# E-Book_Wing_Rev_A.net
KiCad netlist of a schematic drawn in EAGLE
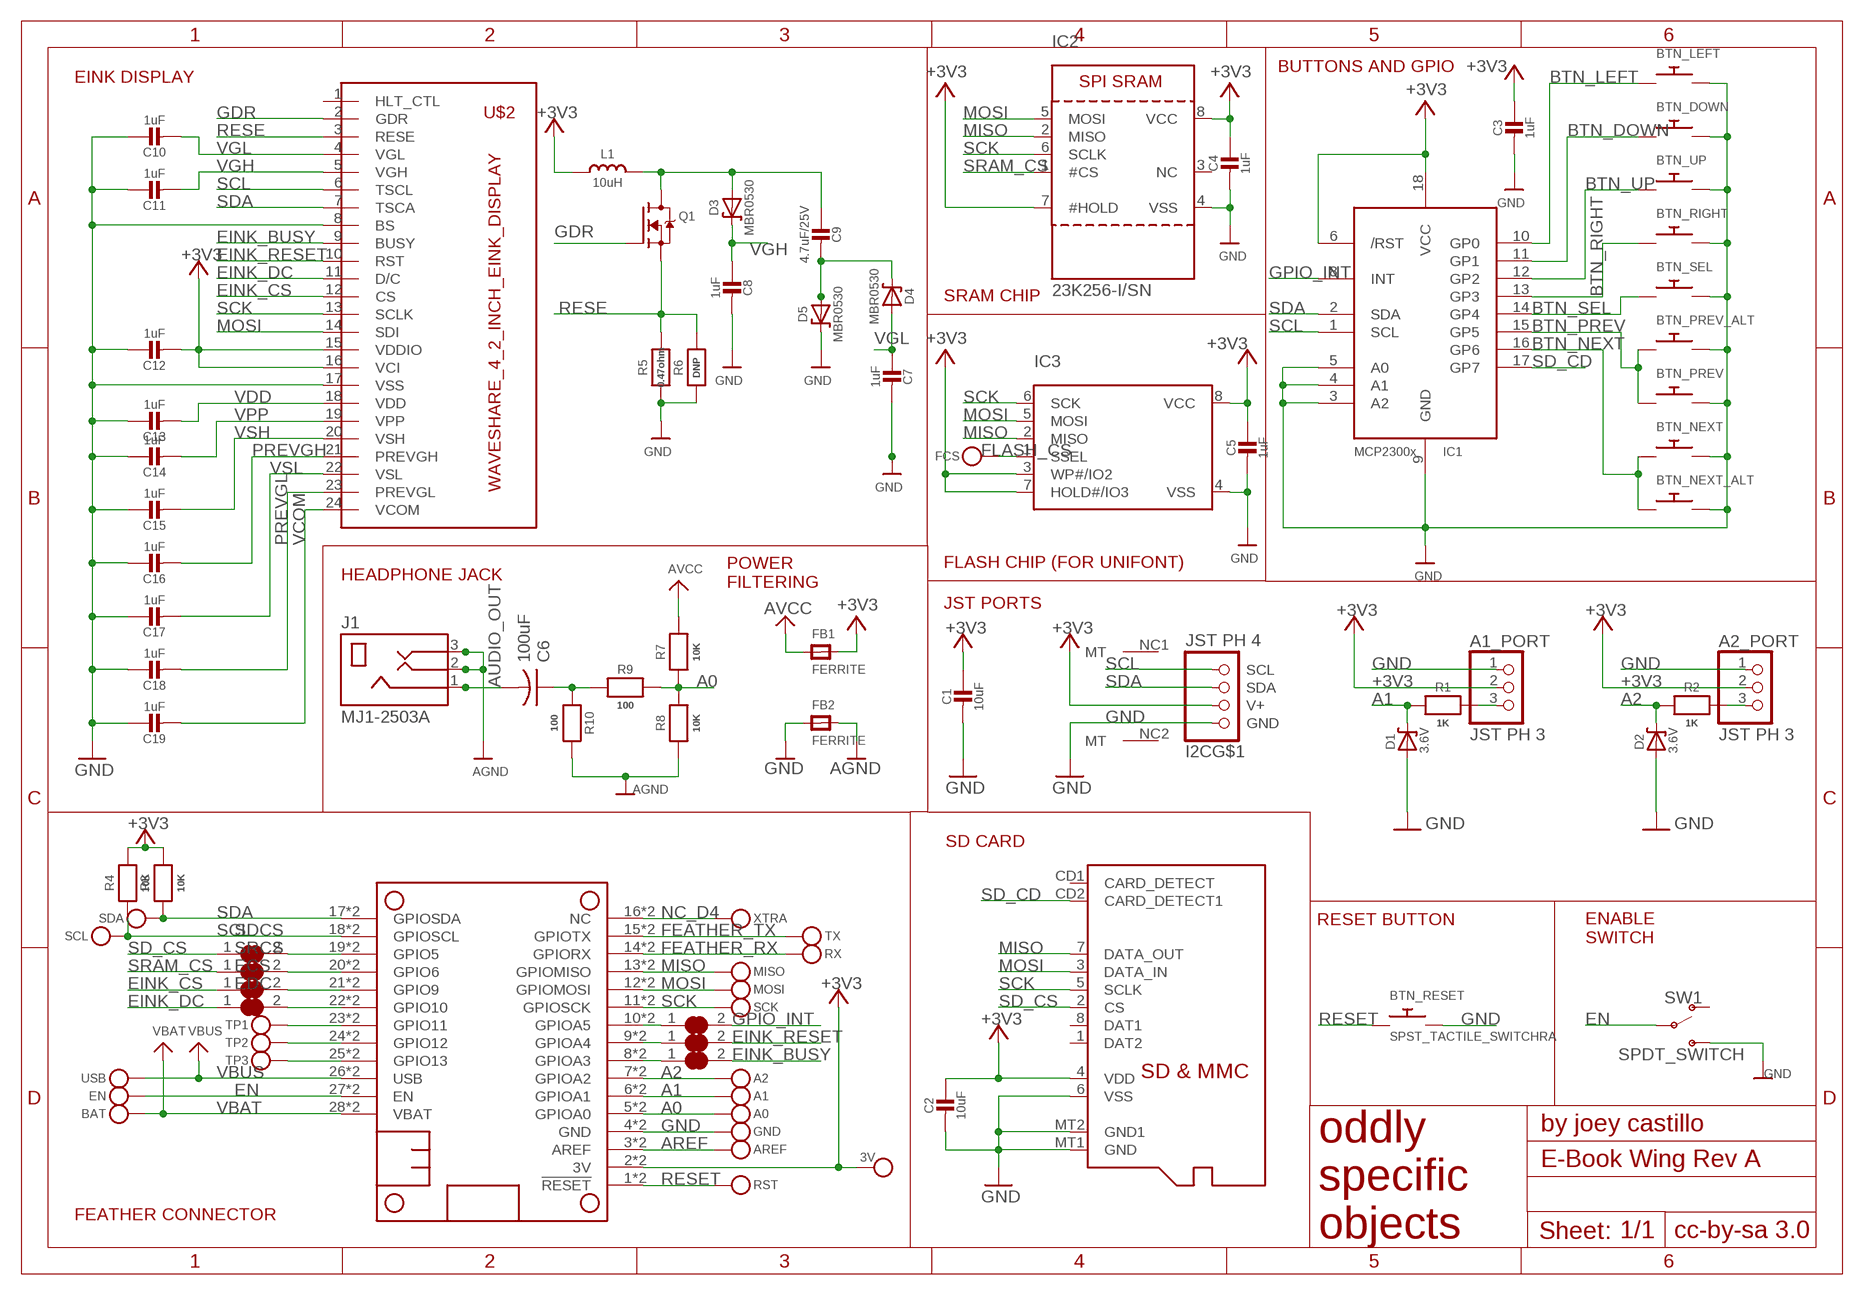
[diagram p0: schematic, sheet 1]

(export (version "E")
  (design (tool "Eeschema 10.0.6"))
  (components
    (comp (ref "3V")
      (value "MICROBUILDER_TESTPOINT1.5X2.0MM_NOCREAM")
      (footprint "eagle-import:MICROBUILDER_PAD-1.5X2.0")
      (libsource (lib "eagle-import") (part "MICROBUILDER_TESTPOINT1.5X2.0MM_NOCREAM"))
    )
    (comp (ref "A0")
      (value "MICROBUILDER_TESTPOINT1.5X2.0MM_NOCREAM")
      (footprint "eagle-import:MICROBUILDER_PAD-1.5X2.0")
      (libsource (lib "eagle-import") (part "MICROBUILDER_TESTPOINT1.5X2.0MM_NOCREAM"))
    )
    (comp (ref "A1")
      (value "MICROBUILDER_TESTPOINT1.5X2.0MM_NOCREAM")
      (footprint "eagle-import:MICROBUILDER_PAD-1.5X2.0")
      (libsource (lib "eagle-import") (part "MICROBUILDER_TESTPOINT1.5X2.0MM_NOCREAM"))
    )
    (comp (ref "A1_PORT")
      (value "JST PH 3")
      (footprint "eagle-import:JSTPH3")
      (libsource (lib "eagle-import") (part "CON_JST_PH_3PIN"))
    )
    (comp (ref "A2")
      (value "MICROBUILDER_TESTPOINT1.5X2.0MM_NOCREAM")
      (footprint "eagle-import:MICROBUILDER_PAD-1.5X2.0")
      (libsource (lib "eagle-import") (part "MICROBUILDER_TESTPOINT1.5X2.0MM_NOCREAM"))
    )
    (comp (ref "A2_PORT")
      (value "JST PH 3")
      (footprint "eagle-import:JSTPH3")
      (libsource (lib "eagle-import") (part "CON_JST_PH_3PIN"))
    )
    (comp (ref "AREF")
      (value "MICROBUILDER_TESTPOINT1.5X2.0MM_NOCREAM")
      (footprint "eagle-import:MICROBUILDER_PAD-1.5X2.0")
      (libsource (lib "eagle-import") (part "MICROBUILDER_TESTPOINT1.5X2.0MM_NOCREAM"))
    )
    (comp (ref "BAT")
      (value "MICROBUILDER_TESTPOINT1.5X2.0MM_NOCREAM")
      (footprint "eagle-import:MICROBUILDER_PAD-1.5X2.0")
      (libsource (lib "eagle-import") (part "MICROBUILDER_TESTPOINT1.5X2.0MM_NOCREAM"))
    )
    (comp (ref "BTN_DOWN")
      (value "MJTP1250_SPST_SWITCH")
      (footprint "eagle-import:MJTP1250")
      (libsource (lib "eagle-import") (part "MJTP1250_SPST_SWITCH"))
    )
    (comp (ref "BTN_LEFT")
      (value "MJTP1250_SPST_SWITCH")
      (footprint "eagle-import:MJTP1250")
      (libsource (lib "eagle-import") (part "MJTP1250_SPST_SWITCH"))
    )
    (comp (ref "BTN_NEXT")
      (value "MJTP1250_SPST_SWITCH")
      (footprint "eagle-import:MJTP1250")
      (libsource (lib "eagle-import") (part "MJTP1250_SPST_SWITCH"))
    )
    (comp (ref "BTN_NEXT_ALT")
      (value "SPST_TACTILE_SWITCHRA")
      (footprint "eagle-import:TL3330AF130QG")
      (libsource (lib "eagle-import") (part "SPST_TACTILE_SWITCHRA"))
    )
    (comp (ref "BTN_PREV")
      (value "MJTP1250_SPST_SWITCH")
      (footprint "eagle-import:MJTP1250")
      (libsource (lib "eagle-import") (part "MJTP1250_SPST_SWITCH"))
    )
    (comp (ref "BTN_PREV_ALT")
      (value "SPST_TACTILE_SWITCHRA")
      (footprint "eagle-import:TL3330AF130QG")
      (libsource (lib "eagle-import") (part "SPST_TACTILE_SWITCHRA"))
    )
    (comp (ref "BTN_RESET")
      (value "SPST_TACTILE_SWITCHRA")
      (footprint "eagle-import:TL3330AF130QG")
      (libsource (lib "eagle-import") (part "SPST_TACTILE_SWITCHRA"))
    )
    (comp (ref "BTN_RIGHT")
      (value "MJTP1250_SPST_SWITCH")
      (footprint "eagle-import:MJTP1250")
      (libsource (lib "eagle-import") (part "MJTP1250_SPST_SWITCH"))
    )
    (comp (ref "BTN_SEL")
      (value "MJTP1250_SPST_SWITCH")
      (footprint "eagle-import:MJTP1250")
      (libsource (lib "eagle-import") (part "MJTP1250_SPST_SWITCH"))
    )
    (comp (ref "BTN_UP")
      (value "MJTP1250_SPST_SWITCH")
      (footprint "eagle-import:MJTP1250")
      (libsource (lib "eagle-import") (part "MJTP1250_SPST_SWITCH"))
    )
    (comp (ref "C1")
      (value "10uF")
      (footprint "eagle-import:0805-NO")
      (libsource (lib "eagle-import") (part "CAP_CERAMIC0805-NOOUTLINE"))
    )
    (comp (ref "C2")
      (value "10uF")
      (footprint "eagle-import:0805_10MGAP")
      (libsource (lib "eagle-import") (part "CAP_CERAMIC0805_10MGAP"))
    )
    (comp (ref "C3")
      (value "1uF")
      (footprint "eagle-import:0805_10MGAP")
      (libsource (lib "eagle-import") (part "CAP_CERAMIC0805_10MGAP"))
    )
    (comp (ref "C4")
      (value "1uF")
      (footprint "eagle-import:0805_10MGAP")
      (libsource (lib "eagle-import") (part "CAP_CERAMIC0805_10MGAP"))
    )
    (comp (ref "C5")
      (value "1uF")
      (footprint "eagle-import:0805_10MGAP")
      (libsource (lib "eagle-import") (part "CAP_CERAMIC0805_10MGAP"))
    )
    (comp (ref "C6")
      (value "100uF")
      (footprint "eagle-import:C1210")
      (libsource (lib "eagle-import") (part "C-USC1210"))
    )
    (comp (ref "C7")
      (value "1uF")
      (footprint "eagle-import:0805-NO")
      (libsource (lib "eagle-import") (part "CAP_CERAMIC0805-NOOUTLINE"))
    )
    (comp (ref "C8")
      (value "1uF")
      (footprint "eagle-import:0805-NO")
      (libsource (lib "eagle-import") (part "CAP_CERAMIC0805-NOOUTLINE"))
    )
    (comp (ref "C9")
      (value "4.7uF/25V")
      (footprint "eagle-import:0805-NO")
      (libsource (lib "eagle-import") (part "CAP_CERAMIC0805-NOOUTLINE"))
    )
    (comp (ref "C10")
      (value "1uF")
      (footprint "eagle-import:0805-NO")
      (libsource (lib "eagle-import") (part "CAP_CERAMIC0805-NOOUTLINE"))
    )
    (comp (ref "C11")
      (value "1uF")
      (footprint "eagle-import:0805-NO")
      (libsource (lib "eagle-import") (part "CAP_CERAMIC0805-NOOUTLINE"))
    )
    (comp (ref "C12")
      (value "1uF")
      (footprint "eagle-import:0805-NO")
      (libsource (lib "eagle-import") (part "CAP_CERAMIC0805-NOOUTLINE"))
    )
    (comp (ref "C13")
      (value "1uF")
      (footprint "eagle-import:0805-NO")
      (libsource (lib "eagle-import") (part "CAP_CERAMIC0805-NOOUTLINE"))
    )
    (comp (ref "C14")
      (value "1uF")
      (footprint "eagle-import:0805-NO")
      (libsource (lib "eagle-import") (part "CAP_CERAMIC0805-NOOUTLINE"))
    )
    (comp (ref "C15")
      (value "1uF")
      (footprint "eagle-import:0805-NO")
      (libsource (lib "eagle-import") (part "CAP_CERAMIC0805-NOOUTLINE"))
    )
    (comp (ref "C16")
      (value "1uF")
      (footprint "eagle-import:0805-NO")
      (libsource (lib "eagle-import") (part "CAP_CERAMIC0805-NOOUTLINE"))
    )
    (comp (ref "C17")
      (value "1uF")
      (footprint "eagle-import:0805-NO")
      (libsource (lib "eagle-import") (part "CAP_CERAMIC0805-NOOUTLINE"))
    )
    (comp (ref "C18")
      (value "1uF")
      (footprint "eagle-import:0805-NO")
      (libsource (lib "eagle-import") (part "CAP_CERAMIC0805-NOOUTLINE"))
    )
    (comp (ref "C19")
      (value "1uF")
      (footprint "eagle-import:0805-NO")
      (libsource (lib "eagle-import") (part "CAP_CERAMIC0805-NOOUTLINE"))
    )
    (comp (ref "D1")
      (value "3.6V")
      (footprint "eagle-import:SOD-123")
      (libsource (lib "eagle-import") (part "DIODE-ZENERSOD123"))
    )
    (comp (ref "D2")
      (value "3.6V")
      (footprint "eagle-import:SOD-123")
      (libsource (lib "eagle-import") (part "DIODE-ZENERSOD123"))
    )
    (comp (ref "D3")
      (value "MBR0530")
      (footprint "eagle-import:SOD-123")
      (libsource (lib "eagle-import") (part "DIODE-SCHOTTKYSOD-123"))
    )
    (comp (ref "D4")
      (value "MBR0530")
      (footprint "eagle-import:SOD-123")
      (libsource (lib "eagle-import") (part "DIODE-SCHOTTKYSOD-123"))
    )
    (comp (ref "D5")
      (value "MBR0530")
      (footprint "eagle-import:SOD-123")
      (libsource (lib "eagle-import") (part "DIODE-SCHOTTKYSOD-123"))
    )
    (comp (ref "EBSY")
      (value "MICROBUILDER_SOLDERJUMPER_CLOSED")
      (footprint "eagle-import:MICROBUILDER_SOLDERJUMPER_CLOSEDWIRE")
      (libsource (lib "eagle-import") (part "MICROBUILDER_SOLDERJUMPER_CLOSED"))
    )
    (comp (ref "ECS")
      (value "MICROBUILDER_SOLDERJUMPER_CLOSED")
      (footprint "eagle-import:MICROBUILDER_SOLDERJUMPER_CLOSEDWIRE")
      (libsource (lib "eagle-import") (part "MICROBUILDER_SOLDERJUMPER_CLOSED"))
    )
    (comp (ref "EDC")
      (value "MICROBUILDER_SOLDERJUMPER_CLOSED")
      (footprint "eagle-import:MICROBUILDER_SOLDERJUMPER_CLOSEDWIRE")
      (libsource (lib "eagle-import") (part "MICROBUILDER_SOLDERJUMPER_CLOSED"))
    )
    (comp (ref "EN")
      (value "MICROBUILDER_TESTPOINT1.5X2.0MM_NOCREAM")
      (footprint "eagle-import:MICROBUILDER_PAD-1.5X2.0")
      (libsource (lib "eagle-import") (part "MICROBUILDER_TESTPOINT1.5X2.0MM_NOCREAM"))
    )
    (comp (ref "ERST")
      (value "MICROBUILDER_SOLDERJUMPER_CLOSED")
      (footprint "eagle-import:MICROBUILDER_SOLDERJUMPER_CLOSEDWIRE")
      (libsource (lib "eagle-import") (part "MICROBUILDER_SOLDERJUMPER_CLOSED"))
    )
    (comp (ref "FB1")
      (value "FERRITE")
      (footprint "eagle-import:0805")
      (libsource (lib "eagle-import") (part "FERRITE0805"))
    )
    (comp (ref "FB2")
      (value "FERRITE")
      (footprint "eagle-import:0805")
      (libsource (lib "eagle-import") (part "FERRITE0805"))
    )
    (comp (ref "FCS")
      (value "MICROBUILDER_TESTPOINTPAD1MM")
      (footprint "eagle-import:MICROBUILDER_TESTPOINT_PAD_1MM")
      (libsource (lib "eagle-import") (part "MICROBUILDER_TESTPOINTPAD1MM"))
    )
    (comp (ref "GND")
      (value "MICROBUILDER_TESTPOINT1.5X2.0MM_NOCREAM")
      (footprint "eagle-import:MICROBUILDER_PAD-1.5X2.0")
      (libsource (lib "eagle-import") (part "MICROBUILDER_TESTPOINT1.5X2.0MM_NOCREAM"))
    )
    (comp (ref "I2C")
      (value "JST PH 4")
      (footprint "eagle-import:JSTPH4")
      (libsource (lib "eagle-import") (part "STEMMA_I2C_RASMT"))
    )
    (comp (ref "IC1")
      (value "MCP23008/SO")
      (footprint "eagle-import:SO18W")
      (libsource (lib "eagle-import") (part "MCP23008/SO"))
    )
    (comp (ref "IC2")
      (value "23K256-I/SN")
      (footprint "eagle-import:SOIC8_150MIL")
      (libsource (lib "eagle-import") (part "SRAM_SPI_SOIC8"))
    )
    (comp (ref "IC3")
      (value "MICROBUILDER_SPIFLASH_SOIC8")
      (footprint "eagle-import:MICROBUILDER_SOIC8_150MIL")
      (libsource (lib "eagle-import") (part "MICROBUILDER_SPIFLASH_SOIC8"))
    )
    (comp (ref "INT")
      (value "MICROBUILDER_SOLDERJUMPER_CLOSED")
      (footprint "eagle-import:MICROBUILDER_SOLDERJUMPER_CLOSEDWIRE")
      (libsource (lib "eagle-import") (part "MICROBUILDER_SOLDERJUMPER_CLOSED"))
    )
    (comp (ref "J1")
      (value "MJ1-2503A")
      (footprint "eagle-import:CUI_MJ1-2503A")
      (fields (field (name "DIGI-KEY_PART_NUMBER") "CP1-2503AM-ND") (field (name "MF") "CUI Inc."))
      (libsource (lib "eagle-import") (part "MJ1-2503A"))
    )
    (comp (ref "L1")
      (value "10uH")
      (footprint "eagle-import:INDUCTOR_4X4MM_NR401")
      (libsource (lib "eagle-import") (part "INDUCTORNR401"))
    )
    (comp (ref "MICROSD")
      (value "MICROSD")
      (footprint "eagle-import:MICROSD")
      (libsource (lib "eagle-import") (part "MICROSD"))
    )
    (comp (ref "MISO")
      (value "MICROBUILDER_TESTPOINT1.5X2.0MM_NOCREAM")
      (footprint "eagle-import:MICROBUILDER_PAD-1.5X2.0")
      (libsource (lib "eagle-import") (part "MICROBUILDER_TESTPOINT1.5X2.0MM_NOCREAM"))
    )
    (comp (ref "MOSI")
      (value "MICROBUILDER_TESTPOINT1.5X2.0MM_NOCREAM")
      (footprint "eagle-import:MICROBUILDER_PAD-1.5X2.0")
      (libsource (lib "eagle-import") (part "MICROBUILDER_TESTPOINT1.5X2.0MM_NOCREAM"))
    )
    (comp (ref "MS1")
      (value "MICROBUILDER_FEATHERWING_SMTDUAL")
      (footprint "eagle-import:MICROBUILDER_FEATHERWING_SMT2")
      (libsource (lib "eagle-import") (part "MICROBUILDER_FEATHERWING_SMTDUAL"))
    )
    (comp (ref "Q1")
      (value "IRLML0100")
      (footprint "eagle-import:SOT23-3")
      (libsource (lib "eagle-import") (part "IRLML2060TRPBF"))
    )
    (comp (ref "R1")
      (value "1K")
      (footprint "eagle-import:_0805MP")
      (libsource (lib "eagle-import") (part "RESISTOR_0805MP"))
    )
    (comp (ref "R2")
      (value "1K")
      (footprint "eagle-import:_0805MP")
      (libsource (lib "eagle-import") (part "RESISTOR_0805MP"))
    )
    (comp (ref "R3")
      (value "10K")
      (footprint "eagle-import:_0805MP")
      (libsource (lib "eagle-import") (part "RESISTOR_0805MP"))
    )
    (comp (ref "R4")
      (value "10K")
      (footprint "eagle-import:_0805MP")
      (libsource (lib "eagle-import") (part "RESISTOR_0805MP"))
    )
    (comp (ref "R5")
      (value "0.47ohm")
      (footprint "eagle-import:0805_10MGAP")
      (libsource (lib "eagle-import") (part "RESISTOR0805_10MGAP"))
    )
    (comp (ref "R6")
      (value "DNP")
      (footprint "eagle-import:0805_10MGAP")
      (libsource (lib "eagle-import") (part "RESISTOR0805_10MGAP"))
    )
    (comp (ref "R7")
      (value "10K")
      (footprint "eagle-import:_0805MP")
      (libsource (lib "eagle-import") (part "RESISTOR_0805MP"))
    )
    (comp (ref "R8")
      (value "10K")
      (footprint "eagle-import:_0805MP")
      (libsource (lib "eagle-import") (part "RESISTOR_0805MP"))
    )
    (comp (ref "R9")
      (value "100")
      (footprint "eagle-import:_0805MP")
      (libsource (lib "eagle-import") (part "RESISTOR_0805MP"))
    )
    (comp (ref "R10")
      (value "100")
      (footprint "eagle-import:_0805MP")
      (libsource (lib "eagle-import") (part "RESISTOR_0805MP"))
    )
    (comp (ref "RST")
      (value "MICROBUILDER_TESTPOINT1.5X2.0MM_NOCREAM")
      (footprint "eagle-import:MICROBUILDER_PAD-1.5X2.0")
      (libsource (lib "eagle-import") (part "MICROBUILDER_TESTPOINT1.5X2.0MM_NOCREAM"))
    )
    (comp (ref "RX")
      (value "MICROBUILDER_TESTPOINT1.5X2.0MM_NOCREAM")
      (footprint "eagle-import:MICROBUILDER_PAD-1.5X2.0")
      (libsource (lib "eagle-import") (part "MICROBUILDER_TESTPOINT1.5X2.0MM_NOCREAM"))
    )
    (comp (ref "SCK")
      (value "MICROBUILDER_TESTPOINT1.5X2.0MM_NOCREAM")
      (footprint "eagle-import:MICROBUILDER_PAD-1.5X2.0")
      (libsource (lib "eagle-import") (part "MICROBUILDER_TESTPOINT1.5X2.0MM_NOCREAM"))
    )
    (comp (ref "SCL")
      (value "MICROBUILDER_TESTPOINT1.5X2.0MM_NOCREAM")
      (footprint "eagle-import:MICROBUILDER_PAD-1.5X2.0")
      (libsource (lib "eagle-import") (part "MICROBUILDER_TESTPOINT1.5X2.0MM_NOCREAM"))
    )
    (comp (ref "SDA")
      (value "MICROBUILDER_TESTPOINT1.5X2.0MM_NOCREAM")
      (footprint "eagle-import:MICROBUILDER_PAD-1.5X2.0")
      (libsource (lib "eagle-import") (part "MICROBUILDER_TESTPOINT1.5X2.0MM_NOCREAM"))
    )
    (comp (ref "SDCS")
      (value "MICROBUILDER_SOLDERJUMPER_CLOSED")
      (footprint "eagle-import:MICROBUILDER_SOLDERJUMPER_CLOSEDWIRE")
      (libsource (lib "eagle-import") (part "MICROBUILDER_SOLDERJUMPER_CLOSED"))
    )
    (comp (ref "SRCS")
      (value "MICROBUILDER_SOLDERJUMPER_CLOSED")
      (footprint "eagle-import:MICROBUILDER_SOLDERJUMPER_CLOSEDWIRE")
      (libsource (lib "eagle-import") (part "MICROBUILDER_SOLDERJUMPER_CLOSED"))
    )
    (comp (ref "SW1")
      (value "SPDT_SWITCH")
      (footprint "eagle-import:A10767")
      (libsource (lib "eagle-import") (part "SPDT_SWITCH"))
    )
    (comp (ref "TP1")
      (value "MICROBUILDER_TESTPOINT1.5X2.0MM_NOCREAM")
      (footprint "eagle-import:MICROBUILDER_PAD-1.5X2.0")
      (libsource (lib "eagle-import") (part "MICROBUILDER_TESTPOINT1.5X2.0MM_NOCREAM"))
    )
    (comp (ref "TP2")
      (value "MICROBUILDER_TESTPOINT1.5X2.0MM_NOCREAM")
      (footprint "eagle-import:MICROBUILDER_PAD-1.5X2.0")
      (libsource (lib "eagle-import") (part "MICROBUILDER_TESTPOINT1.5X2.0MM_NOCREAM"))
    )
    (comp (ref "TP3")
      (value "MICROBUILDER_TESTPOINT1.5X2.0MM_NOCREAM")
      (footprint "eagle-import:MICROBUILDER_PAD-1.5X2.0")
      (libsource (lib "eagle-import") (part "MICROBUILDER_TESTPOINT1.5X2.0MM_NOCREAM"))
    )
    (comp (ref "TX")
      (value "MICROBUILDER_TESTPOINT1.5X2.0MM_NOCREAM")
      (footprint "eagle-import:MICROBUILDER_PAD-1.5X2.0")
      (libsource (lib "eagle-import") (part "MICROBUILDER_TESTPOINT1.5X2.0MM_NOCREAM"))
    )
    (comp (ref "U$2")
      (value "WAVESHARE_4_2_INCH_EINK_DISPLAY")
      (footprint "eagle-import:EINK_DISPLAY_4_2IN")
      (libsource (lib "eagle-import") (part "WAVESHARE_4_2_INCH_EINK_DISPLAY"))
    )
    (comp (ref "USB")
      (value "MICROBUILDER_TESTPOINT1.5X2.0MM_NOCREAM")
      (footprint "eagle-import:MICROBUILDER_PAD-1.5X2.0")
      (libsource (lib "eagle-import") (part "MICROBUILDER_TESTPOINT1.5X2.0MM_NOCREAM"))
    )
    (comp (ref "XTRA")
      (value "MICROBUILDER_TESTPOINT1.5X2.0MM_NOCREAM")
      (footprint "eagle-import:MICROBUILDER_PAD-1.5X2.0")
      (libsource (lib "eagle-import") (part "MICROBUILDER_TESTPOINT1.5X2.0MM_NOCREAM"))
    )
  )
  (nets
    (net (code "1") (name "+3V3") (class "Default")
      (node (ref "3V") (pin "P$1") (pinfunction "P$1_P$1") (pintype "bidirectional"))
      (node (ref "A1_PORT") (pin "2") (pinfunction "2_2") (pintype "passive"))
      (node (ref "A2_PORT") (pin "2") (pinfunction "2_2") (pintype "passive"))
      (node (ref "C1") (pin "1") (pinfunction "1_1") (pintype "passive"))
      (node (ref "C12") (pin "2") (pinfunction "2_2") (pintype "passive"))
      (node (ref "C2") (pin "1") (pinfunction "1_1") (pintype "passive"))
      (node (ref "C3") (pin "1") (pinfunction "1_1") (pintype "passive"))
      (node (ref "C4") (pin "1") (pinfunction "1_1") (pintype "passive"))
      (node (ref "C5") (pin "1") (pinfunction "1_1") (pintype "passive"))
      (node (ref "FB1") (pin "2") (pinfunction "P$2_2") (pintype "passive"))
      (node (ref "I2C") (pin "2") (pinfunction "V+_2") (pintype "passive"))
      (node (ref "IC1") (pin "18") (pinfunction "VCC_18") (pintype "power_in"))
      (node (ref "IC1") (pin "6") (pinfunction "/RST_6") (pintype "input"))
      (node (ref "IC2") (pin "7") (pinfunction "#HOLD_7") (pintype "input"))
      (node (ref "IC2") (pin "8") (pinfunction "VCC_8") (pintype "power_in"))
      (node (ref "IC3") (pin "3") (pinfunction "WP#/IO2_3") (pintype "bidirectional"))
      (node (ref "IC3") (pin "7") (pinfunction "HOLD#/IO3_7") (pintype "bidirectional"))
      (node (ref "IC3") (pin "8") (pinfunction "VCC_8") (pintype "bidirectional"))
      (node (ref "L1") (pin "P$2") (pinfunction "2_P$2") (pintype "passive"))
      (node (ref "MICROSD") (pin "4") (pinfunction "VDD_4") (pintype "power_in"))
      (node (ref "MS1") (pin "2") (pinfunction "3V_2") (pintype "power_in"))
      (node (ref "MS1") (pin "2'") (pinfunction "3V_2'") (pintype "power_in"))
      (node (ref "R3") (pin "1") (pinfunction "1_1") (pintype "passive"))
      (node (ref "R4") (pin "1") (pinfunction "1_1") (pintype "passive"))
      (node (ref "U$2") (pin "15") (pinfunction "VDDIO_15") (pintype "bidirectional"))
      (node (ref "U$2") (pin "16") (pinfunction "VCI_16") (pintype "bidirectional"))
    )
    (net (code "2") (name "/A0") (class "Default")
      (node (ref "A0") (pin "P$1") (pinfunction "P$1_P$1") (pintype "bidirectional"))
      (node (ref "MS1") (pin "5") (pinfunction "GPIOA0_5") (pintype "bidirectional"))
      (node (ref "MS1") (pin "5'") (pinfunction "GPIOA0_5'") (pintype "bidirectional"))
      (node (ref "R7") (pin "2") (pinfunction "2_2") (pintype "passive"))
      (node (ref "R8") (pin "1") (pinfunction "1_1") (pintype "passive"))
      (node (ref "R9") (pin "1") (pinfunction "1_1") (pintype "passive"))
    )
    (net (code "3") (name "/A1") (class "Default")
      (node (ref "A1") (pin "P$1") (pinfunction "P$1_P$1") (pintype "bidirectional"))
      (node (ref "D1") (pin "C") (pinfunction "C_C") (pintype "passive"))
      (node (ref "MS1") (pin "6") (pinfunction "GPIOA1_6") (pintype "bidirectional"))
      (node (ref "MS1") (pin "6'") (pinfunction "GPIOA1_6'") (pintype "bidirectional"))
      (node (ref "R1") (pin "2") (pinfunction "2_2") (pintype "passive"))
    )
    (net (code "4") (name "/A2") (class "Default")
      (node (ref "A2") (pin "P$1") (pinfunction "P$1_P$1") (pintype "bidirectional"))
      (node (ref "D2") (pin "C") (pinfunction "C_C") (pintype "passive"))
      (node (ref "MS1") (pin "7") (pinfunction "GPIOA2_7") (pintype "bidirectional"))
      (node (ref "MS1") (pin "7'") (pinfunction "GPIOA2_7'") (pintype "bidirectional"))
      (node (ref "R2") (pin "2") (pinfunction "2_2") (pintype "passive"))
    )
    (net (code "5") (name "/AREF") (class "Default")
      (node (ref "AREF") (pin "P$1") (pinfunction "P$1_P$1") (pintype "bidirectional"))
      (node (ref "MS1") (pin "3") (pinfunction "AREF_3") (pintype "passive"))
      (node (ref "MS1") (pin "3'") (pinfunction "AREF_3'") (pintype "passive"))
    )
    (net (code "6") (name "/AUDIO_OUT") (class "Default")
      (node (ref "C6") (pin "2") (pinfunction "2_2") (pintype "passive"))
      (node (ref "J1") (pin "1") (pinfunction "1_1") (pintype "passive"))
    )
    (net (code "7") (name "/BTN_DOWN") (class "Default")
      (node (ref "BTN_DOWN") (pin "P$1") (pinfunction "P$1_P$1") (pintype "passive"))
      (node (ref "IC1") (pin "11") (pinfunction "GP1_11") (pintype "bidirectional"))
    )
    (net (code "8") (name "/BTN_LEFT") (class "Default")
      (node (ref "BTN_LEFT") (pin "P$1") (pinfunction "P$1_P$1") (pintype "passive"))
      (node (ref "IC1") (pin "10") (pinfunction "GP0_10") (pintype "bidirectional"))
    )
    (net (code "9") (name "/BTN_NEXT") (class "Default")
      (node (ref "BTN_NEXT") (pin "P$1") (pinfunction "P$1_P$1") (pintype "passive"))
      (node (ref "BTN_NEXT_ALT") (pin "P$1") (pinfunction "P$1_P$1") (pintype "passive"))
      (node (ref "IC1") (pin "16") (pinfunction "GP6_16") (pintype "bidirectional"))
    )
    (net (code "10") (name "/BTN_PREV") (class "Default")
      (node (ref "BTN_PREV") (pin "P$1") (pinfunction "P$1_P$1") (pintype "passive"))
      (node (ref "BTN_PREV_ALT") (pin "P$1") (pinfunction "P$1_P$1") (pintype "passive"))
      (node (ref "IC1") (pin "15") (pinfunction "GP5_15") (pintype "bidirectional"))
    )
    (net (code "11") (name "/BTN_RIGHT") (class "Default")
      (node (ref "BTN_RIGHT") (pin "P$1") (pinfunction "P$1_P$1") (pintype "passive"))
      (node (ref "IC1") (pin "13") (pinfunction "GP3_13") (pintype "bidirectional"))
    )
    (net (code "12") (name "/BTN_SEL") (class "Default")
      (node (ref "BTN_SEL") (pin "P$1") (pinfunction "P$1_P$1") (pintype "passive"))
      (node (ref "IC1") (pin "14") (pinfunction "GP4_14") (pintype "bidirectional"))
    )
    (net (code "13") (name "/BTN_UP") (class "Default")
      (node (ref "BTN_UP") (pin "P$1") (pinfunction "P$1_P$1") (pintype "passive"))
      (node (ref "IC1") (pin "12") (pinfunction "GP2_12") (pintype "bidirectional"))
    )
    (net (code "14") (name "/EINK_BUSY") (class "Default")
      (node (ref "EBSY") (pin "2") (pinfunction "2_2") (pintype "passive"))
      (node (ref "U$2") (pin "9") (pinfunction "BUSY_9") (pintype "bidirectional"))
    )
    (net (code "15") (name "/EINK_CS") (class "Default")
      (node (ref "ECS") (pin "1") (pinfunction "1_1") (pintype "passive"))
      (node (ref "U$2") (pin "12") (pinfunction "CS_12") (pintype "bidirectional"))
    )
    (net (code "16") (name "/EINK_DC") (class "Default")
      (node (ref "EDC") (pin "1") (pinfunction "1_1") (pintype "passive"))
      (node (ref "U$2") (pin "11") (pinfunction "D/C_11") (pintype "bidirectional"))
    )
    (net (code "17") (name "/EINK_RESET") (class "Default")
      (node (ref "ERST") (pin "2") (pinfunction "2_2") (pintype "passive"))
      (node (ref "U$2") (pin "10") (pinfunction "RST_10") (pintype "bidirectional"))
    )
    (net (code "18") (name "/EN") (class "Default")
      (node (ref "EN") (pin "P$1") (pinfunction "P$1_P$1") (pintype "bidirectional"))
      (node (ref "MS1") (pin "27") (pinfunction "EN_27") (pintype "passive"))
      (node (ref "MS1") (pin "27'") (pinfunction "EN_27'") (pintype "passive"))
      (node (ref "SW1") (pin "P$2") (pinfunction "P_P$2") (pintype "passive"))
    )
    (net (code "19") (name "/FEATHER_RX") (class "Default")
      (node (ref "MS1") (pin "14") (pinfunction "GPIORX_14") (pintype "bidirectional"))
      (node (ref "MS1") (pin "14'") (pinfunction "GPIORX_14'") (pintype "bidirectional"))
      (node (ref "RX") (pin "P$1") (pinfunction "P$1_P$1") (pintype "bidirectional"))
    )
    (net (code "20") (name "/FEATHER_TX") (class "Default")
      (node (ref "MS1") (pin "15") (pinfunction "GPIOTX_15") (pintype "bidirectional"))
      (node (ref "MS1") (pin "15'") (pinfunction "GPIOTX_15'") (pintype "bidirectional"))
      (node (ref "TX") (pin "P$1") (pinfunction "P$1_P$1") (pintype "bidirectional"))
    )
    (net (code "21") (name "/FLASH_CS") (class "Default")
      (node (ref "FCS") (pin "P$1") (pinfunction "P$1_P$1") (pintype "bidirectional"))
      (node (ref "IC3") (pin "1") (pinfunction "SSEL_1") (pintype "bidirectional"))
    )
    (net (code "22") (name "/GDR") (class "Default")
      (node (ref "Q1") (pin "1") (pinfunction "G_1") (pintype "bidirectional"))
      (node (ref "U$2") (pin "2") (pinfunction "GDR_2") (pintype "bidirectional"))
    )
    (net (code "23") (name "/GPIO_INT") (class "Default")
      (node (ref "IC1") (pin "8") (pinfunction "INT_8") (pintype "output"))
      (node (ref "INT") (pin "2") (pinfunction "2_2") (pintype "passive"))
    )
    (net (code "24") (name "/MISO") (class "Default")
      (node (ref "IC2") (pin "2") (pinfunction "MISO_2") (pintype "output"))
      (node (ref "IC3") (pin "2") (pinfunction "MISO_2") (pintype "bidirectional"))
      (node (ref "MICROSD") (pin "7") (pinfunction "DATA_OUT_7") (pintype "output"))
      (node (ref "MISO") (pin "P$1") (pinfunction "P$1_P$1") (pintype "bidirectional"))
      (node (ref "MS1") (pin "13") (pinfunction "GPIOMISO_13") (pintype "bidirectional"))
      (node (ref "MS1") (pin "13'") (pinfunction "GPIOMISO_13'") (pintype "bidirectional"))
    )
    (net (code "25") (name "/MOSI") (class "Default")
      (node (ref "IC2") (pin "5") (pinfunction "MOSI_5") (pintype "input"))
      (node (ref "IC3") (pin "5") (pinfunction "MOSI_5") (pintype "bidirectional"))
      (node (ref "MICROSD") (pin "3") (pinfunction "DATA_IN_3") (pintype "input"))
      (node (ref "MOSI") (pin "P$1") (pinfunction "P$1_P$1") (pintype "bidirectional"))
      (node (ref "MS1") (pin "12") (pinfunction "GPIOMOSI_12") (pintype "bidirectional"))
      (node (ref "MS1") (pin "12'") (pinfunction "GPIOMOSI_12'") (pintype "bidirectional"))
      (node (ref "U$2") (pin "14") (pinfunction "SDI_14") (pintype "bidirectional"))
    )
    (net (code "26") (name "/NC_D4") (class "Default")
      (node (ref "MS1") (pin "16") (pinfunction "NC_16") (pintype "passive"))
      (node (ref "MS1") (pin "16'") (pinfunction "NC_16'") (pintype "passive"))
      (node (ref "XTRA") (pin "P$1") (pinfunction "P$1_P$1") (pintype "bidirectional"))
    )
    (net (code "27") (name "/PREVGH") (class "Default")
      (node (ref "C16") (pin "2") (pinfunction "2_2") (pintype "passive"))
      (node (ref "U$2") (pin "21") (pinfunction "PREVGH_21") (pintype "bidirectional"))
    )
    (net (code "28") (name "/PREVGL") (class "Default")
      (node (ref "C18") (pin "2") (pinfunction "2_2") (pintype "passive"))
      (node (ref "U$2") (pin "23") (pinfunction "PREVGL_23") (pintype "bidirectional"))
    )
    (net (code "29") (name "/RESE") (class "Default")
      (node (ref "Q1") (pin "2") (pinfunction "S_2") (pintype "bidirectional"))
      (node (ref "R5") (pin "1") (pinfunction "1_1") (pintype "passive"))
      (node (ref "R6") (pin "1") (pinfunction "1_1") (pintype "passive"))
      (node (ref "U$2") (pin "3") (pinfunction "RESE_3") (pintype "bidirectional"))
    )
    (net (code "30") (name "/RESET") (class "Default")
      (node (ref "BTN_RESET") (pin "P$1") (pinfunction "P$1_P$1") (pintype "passive"))
      (node (ref "MS1") (pin "1") (pinfunction "~{RESET}_1") (pintype "input"))
      (node (ref "MS1") (pin "1'") (pinfunction "~{RESET}_1'") (pintype "input"))
      (node (ref "RST") (pin "P$1") (pinfunction "P$1_P$1") (pintype "bidirectional"))
    )
    (net (code "31") (name "/SCK") (class "Default")
      (node (ref "IC2") (pin "6") (pinfunction "SCLK_6") (pintype "input"))
      (node (ref "IC3") (pin "6") (pinfunction "SCK_6") (pintype "bidirectional"))
      (node (ref "MICROSD") (pin "5") (pinfunction "SCLK_5") (pintype "input"))
      (node (ref "MS1") (pin "11") (pinfunction "GPIOSCK_11") (pintype "bidirectional"))
      (node (ref "MS1") (pin "11'") (pinfunction "GPIOSCK_11'") (pintype "bidirectional"))
      (node (ref "SCK") (pin "P$1") (pinfunction "P$1_P$1") (pintype "bidirectional"))
      (node (ref "U$2") (pin "13") (pinfunction "SCLK_13") (pintype "bidirectional"))
    )
    (net (code "32") (name "/SCL") (class "Default")
      (node (ref "I2C") (pin "4") (pinfunction "SCL_4") (pintype "passive"))
      (node (ref "IC1") (pin "1") (pinfunction "SCL_1") (pintype "bidirectional"))
      (node (ref "MS1") (pin "18") (pinfunction "GPIOSCL_18") (pintype "bidirectional"))
      (node (ref "MS1") (pin "18'") (pinfunction "GPIOSCL_18'") (pintype "bidirectional"))
      (node (ref "R4") (pin "2") (pinfunction "2_2") (pintype "passive"))
      (node (ref "SCL") (pin "P$1") (pinfunction "P$1_P$1") (pintype "bidirectional"))
      (node (ref "U$2") (pin "6") (pinfunction "TSCL_6") (pintype "bidirectional"))
    )
    (net (code "33") (name "/SDA") (class "Default")
      (node (ref "I2C") (pin "3") (pinfunction "SDA_3") (pintype "passive"))
      (node (ref "IC1") (pin "2") (pinfunction "SDA_2") (pintype "bidirectional"))
      (node (ref "MS1") (pin "17") (pinfunction "GPIOSDA_17") (pintype "bidirectional"))
      (node (ref "MS1") (pin "17'") (pinfunction "GPIOSDA_17'") (pintype "bidirectional"))
      (node (ref "R3") (pin "2") (pinfunction "2_2") (pintype "passive"))
      (node (ref "SDA") (pin "P$1") (pinfunction "P$1_P$1") (pintype "bidirectional"))
      (node (ref "U$2") (pin "7") (pinfunction "TSCA_7") (pintype "bidirectional"))
    )
    (net (code "34") (name "/SD_CD") (class "Default")
      (node (ref "IC1") (pin "17") (pinfunction "GP7_17") (pintype "bidirectional"))
      (node (ref "MICROSD") (pin "CD2") (pinfunction "CARD_DETECT1_CD2") (pintype "passive"))
    )
    (net (code "35") (name "/SD_CS") (class "Default")
      (node (ref "MICROSD") (pin "2") (pinfunction "CS_2") (pintype "input"))
      (node (ref "SDCS") (pin "1") (pinfunction "1_1") (pintype "passive"))
    )
    (net (code "36") (name "/SRAM_CS") (class "Default")
      (node (ref "IC2") (pin "1") (pinfunction "#CS_1") (pintype "input"))
      (node (ref "SRCS") (pin "1") (pinfunction "1_1") (pintype "passive"))
    )
    (net (code "37") (name "/VCOM") (class "Default")
      (node (ref "C19") (pin "2") (pinfunction "2_2") (pintype "passive"))
      (node (ref "U$2") (pin "24") (pinfunction "VCOM_24") (pintype "bidirectional"))
    )
    (net (code "38") (name "/VDD") (class "Default")
      (node (ref "C13") (pin "2") (pinfunction "2_2") (pintype "passive"))
      (node (ref "U$2") (pin "18") (pinfunction "VDD_18") (pintype "bidirectional"))
    )
    (net (code "39") (name "/VGH") (class "Default")
      (node (ref "C11") (pin "2") (pinfunction "2_2") (pintype "passive"))
      (node (ref "C8") (pin "1") (pinfunction "1_1") (pintype "passive"))
      (node (ref "D3") (pin "C") (pinfunction "C_C") (pintype "passive"))
      (node (ref "U$2") (pin "5") (pinfunction "VGH_5") (pintype "bidirectional"))
    )
    (net (code "40") (name "/VGL") (class "Default")
      (node (ref "C10") (pin "2") (pinfunction "2_2") (pintype "passive"))
      (node (ref "C7") (pin "1") (pinfunction "1_1") (pintype "passive"))
      (node (ref "D4") (pin "A") (pinfunction "A_A") (pintype "passive"))
      (node (ref "U$2") (pin "4") (pinfunction "VGL_4") (pintype "bidirectional"))
    )
    (net (code "41") (name "/VPP") (class "Default")
      (node (ref "C14") (pin "2") (pinfunction "2_2") (pintype "passive"))
      (node (ref "U$2") (pin "19") (pinfunction "VPP_19") (pintype "bidirectional"))
    )
    (net (code "42") (name "/VSH") (class "Default")
      (node (ref "C15") (pin "2") (pinfunction "2_2") (pintype "passive"))
      (node (ref "U$2") (pin "20") (pinfunction "VSH_20") (pintype "bidirectional"))
    )
    (net (code "43") (name "/VSL") (class "Default")
      (node (ref "C17") (pin "2") (pinfunction "2_2") (pintype "passive"))
      (node (ref "U$2") (pin "22") (pinfunction "VSL_22") (pintype "bidirectional"))
    )
    (net (code "44") (name "AGND") (class "Default")
      (node (ref "FB2") (pin "2") (pinfunction "P$2_2") (pintype "passive"))
      (node (ref "J1") (pin "2") (pinfunction "2_2") (pintype "passive"))
      (node (ref "J1") (pin "3") (pinfunction "3_3") (pintype "passive"))
      (node (ref "R10") (pin "1") (pinfunction "1_1") (pintype "passive"))
      (node (ref "R8") (pin "2") (pinfunction "2_2") (pintype "passive"))
    )
    (net (code "45") (name "AVCC") (class "Default")
      (node (ref "FB1") (pin "1") (pinfunction "P$1_1") (pintype "passive"))
      (node (ref "R7") (pin "1") (pinfunction "1_1") (pintype "passive"))
    )
    (net (code "46") (name "GND") (class "Default")
      (node (ref "A1_PORT") (pin "1") (pinfunction "1_1") (pintype "passive"))
      (node (ref "A2_PORT") (pin "1") (pinfunction "1_1") (pintype "passive"))
      (node (ref "BTN_DOWN") (pin "P$2") (pinfunction "P$2_P$2") (pintype "passive"))
      (node (ref "BTN_LEFT") (pin "P$2") (pinfunction "P$2_P$2") (pintype "passive"))
      (node (ref "BTN_NEXT") (pin "P$2") (pinfunction "P$2_P$2") (pintype "passive"))
      (node (ref "BTN_NEXT_ALT") (pin "P$2") (pinfunction "P$2_P$2") (pintype "passive"))
      (node (ref "BTN_PREV") (pin "P$2") (pinfunction "P$2_P$2") (pintype "passive"))
      (node (ref "BTN_PREV_ALT") (pin "P$2") (pinfunction "P$2_P$2") (pintype "passive"))
      (node (ref "BTN_RESET") (pin "P$2") (pinfunction "P$2_P$2") (pintype "passive"))
      (node (ref "BTN_RIGHT") (pin "P$2") (pinfunction "P$2_P$2") (pintype "passive"))
      (node (ref "BTN_SEL") (pin "P$2") (pinfunction "P$2_P$2") (pintype "passive"))
      (node (ref "BTN_UP") (pin "P$2") (pinfunction "P$2_P$2") (pintype "passive"))
      (node (ref "C1") (pin "2") (pinfunction "2_2") (pintype "passive"))
      (node (ref "C10") (pin "1") (pinfunction "1_1") (pintype "passive"))
      (node (ref "C11") (pin "1") (pinfunction "1_1") (pintype "passive"))
      (node (ref "C12") (pin "1") (pinfunction "1_1") (pintype "passive"))
      (node (ref "C13") (pin "1") (pinfunction "1_1") (pintype "passive"))
      (node (ref "C14") (pin "1") (pinfunction "1_1") (pintype "passive"))
      (node (ref "C15") (pin "1") (pinfunction "1_1") (pintype "passive"))
      (node (ref "C16") (pin "1") (pinfunction "1_1") (pintype "passive"))
      (node (ref "C17") (pin "1") (pinfunction "1_1") (pintype "passive"))
      (node (ref "C18") (pin "1") (pinfunction "1_1") (pintype "passive"))
      (node (ref "C19") (pin "1") (pinfunction "1_1") (pintype "passive"))
      (node (ref "C2") (pin "2") (pinfunction "2_2") (pintype "passive"))
      (node (ref "C3") (pin "2") (pinfunction "2_2") (pintype "passive"))
      (node (ref "C4") (pin "2") (pinfunction "2_2") (pintype "passive"))
      (node (ref "C5") (pin "2") (pinfunction "2_2") (pintype "passive"))
      (node (ref "C7") (pin "2") (pinfunction "2_2") (pintype "passive"))
      (node (ref "C8") (pin "2") (pinfunction "2_2") (pintype "passive"))
      (node (ref "D1") (pin "A") (pinfunction "A_A") (pintype "passive"))
      (node (ref "D2") (pin "A") (pinfunction "A_A") (pintype "passive"))
      (node (ref "D5") (pin "C") (pinfunction "C_C") (pintype "passive"))
      (node (ref "FB2") (pin "1") (pinfunction "P$1_1") (pintype "passive"))
      (node (ref "GND") (pin "P$1") (pinfunction "P$1_P$1") (pintype "bidirectional"))
      (node (ref "I2C") (pin "1") (pinfunction "GND_1") (pintype "passive"))
      (node (ref "IC1") (pin "3") (pinfunction "A2_3") (pintype "input"))
      (node (ref "IC1") (pin "4") (pinfunction "A1_4") (pintype "input"))
      (node (ref "IC1") (pin "5") (pinfunction "A0_5") (pintype "input"))
      (node (ref "IC1") (pin "9") (pinfunction "GND_9") (pintype "power_in"))
      (node (ref "IC2") (pin "4") (pinfunction "VSS_4") (pintype "power_in"))
      (node (ref "IC3") (pin "4") (pinfunction "VSS_4") (pintype "bidirectional"))
      (node (ref "MICROSD") (pin "6") (pinfunction "VSS_6") (pintype "power_in"))
      (node (ref "MICROSD") (pin "MT1") (pinfunction "GND_MT1") (pintype "power_in"))
      (node (ref "MICROSD") (pin "MT2") (pinfunction "GND1_MT2") (pintype "power_in"))
      (node (ref "MS1") (pin "4") (pinfunction "GND_4") (pintype "power_in"))
      (node (ref "MS1") (pin "4'") (pinfunction "GND_4'") (pintype "power_in"))
      (node (ref "R5") (pin "2") (pinfunction "2_2") (pintype "passive"))
      (node (ref "R6") (pin "2") (pinfunction "2_2") (pintype "passive"))
      (node (ref "SW1") (pin "P$3") (pinfunction "S_P$3") (pintype "passive"))
      (node (ref "U$2") (pin "17") (pinfunction "VSS_17") (pintype "bidirectional"))
      (node (ref "U$2") (pin "8") (pinfunction "BS_8") (pintype "bidirectional"))
    )
    (net (code "47") (name "Net-(A1_PORT-Pad3)") (class "Default")
      (node (ref "A1_PORT") (pin "3") (pinfunction "3_3") (pintype "passive"))
      (node (ref "R1") (pin "1") (pinfunction "1_1") (pintype "passive"))
    )
    (net (code "48") (name "Net-(A2_PORT-Pad3)") (class "Default")
      (node (ref "A2_PORT") (pin "3") (pinfunction "3_3") (pintype "passive"))
      (node (ref "R2") (pin "1") (pinfunction "1_1") (pintype "passive"))
    )
    (net (code "49") (name "Net-(C6-Pad1)") (class "Default")
      (node (ref "C6") (pin "1") (pinfunction "1_1") (pintype "passive"))
      (node (ref "R10") (pin "2") (pinfunction "2_2") (pintype "passive"))
      (node (ref "R9") (pin "2") (pinfunction "2_2") (pintype "passive"))
    )
    (net (code "50") (name "Net-(C9-Pad2)") (class "Default")
      (node (ref "C9") (pin "2") (pinfunction "2_2") (pintype "passive"))
      (node (ref "D4") (pin "C") (pinfunction "C_C") (pintype "passive"))
      (node (ref "D5") (pin "A") (pinfunction "A_A") (pintype "passive"))
    )
    (net (code "51") (name "Net-(EBSY-Pad1)") (class "Default")
      (node (ref "EBSY") (pin "1") (pinfunction "1_1") (pintype "passive"))
      (node (ref "MS1") (pin "8") (pinfunction "GPIOA3_8") (pintype "bidirectional"))
      (node (ref "MS1") (pin "8'") (pinfunction "GPIOA3_8'") (pintype "bidirectional"))
    )
    (net (code "52") (name "Net-(ECS-Pad2)") (class "Default")
      (node (ref "ECS") (pin "2") (pinfunction "2_2") (pintype "passive"))
      (node (ref "MS1") (pin "21") (pinfunction "GPIO9_21") (pintype "bidirectional"))
      (node (ref "MS1") (pin "21'") (pinfunction "GPIO9_21'") (pintype "bidirectional"))
    )
    (net (code "53") (name "Net-(EDC-Pad2)") (class "Default")
      (node (ref "EDC") (pin "2") (pinfunction "2_2") (pintype "passive"))
      (node (ref "MS1") (pin "22") (pinfunction "GPIO10_22") (pintype "bidirectional"))
      (node (ref "MS1") (pin "22'") (pinfunction "GPIO10_22'") (pintype "bidirectional"))
    )
    (net (code "54") (name "Net-(ERST-Pad1)") (class "Default")
      (node (ref "ERST") (pin "1") (pinfunction "1_1") (pintype "passive"))
      (node (ref "MS1") (pin "9") (pinfunction "GPIOA4_9") (pintype "bidirectional"))
      (node (ref "MS1") (pin "9'") (pinfunction "GPIOA4_9'") (pintype "bidirectional"))
    )
    (net (code "55") (name "Net-(INT-Pad1)") (class "Default")
      (node (ref "INT") (pin "1") (pinfunction "1_1") (pintype "passive"))
      (node (ref "MS1") (pin "10") (pinfunction "GPIOA5_10") (pintype "bidirectional"))
      (node (ref "MS1") (pin "10'") (pinfunction "GPIOA5_10'") (pintype "bidirectional"))
    )
    (net (code "56") (name "Net-(L1-1)") (class "Default")
      (node (ref "C9") (pin "1") (pinfunction "1_1") (pintype "passive"))
      (node (ref "D3") (pin "A") (pinfunction "A_A") (pintype "passive"))
      (node (ref "L1") (pin "P$1") (pinfunction "1_P$1") (pintype "passive"))
      (node (ref "Q1") (pin "3") (pinfunction "D_3") (pintype "bidirectional"))
    )
    (net (code "57") (name "Net-(MS1-GPIO5-Pad19')") (class "Default")
      (node (ref "MS1") (pin "19") (pinfunction "GPIO5_19") (pintype "bidirectional"))
      (node (ref "MS1") (pin "19'") (pinfunction "GPIO5_19'") (pintype "bidirectional"))
      (node (ref "SDCS") (pin "2") (pinfunction "2_2") (pintype "passive"))
    )
    (net (code "58") (name "Net-(MS1-GPIO6-Pad20')") (class "Default")
      (node (ref "MS1") (pin "20") (pinfunction "GPIO6_20") (pintype "bidirectional"))
      (node (ref "MS1") (pin "20'") (pinfunction "GPIO6_20'") (pintype "bidirectional"))
      (node (ref "SRCS") (pin "2") (pinfunction "2_2") (pintype "passive"))
    )
    (net (code "59") (name "Net-(MS1-GPIO11-Pad23')") (class "Default")
      (node (ref "MS1") (pin "23") (pinfunction "GPIO11_23") (pintype "bidirectional"))
      (node (ref "MS1") (pin "23'") (pinfunction "GPIO11_23'") (pintype "bidirectional"))
      (node (ref "TP1") (pin "P$1") (pinfunction "P$1_P$1") (pintype "bidirectional"))
    )
    (net (code "60") (name "Net-(MS1-GPIO12-Pad24')") (class "Default")
      (node (ref "MS1") (pin "24") (pinfunction "GPIO12_24") (pintype "bidirectional"))
      (node (ref "MS1") (pin "24'") (pinfunction "GPIO12_24'") (pintype "bidirectional"))
      (node (ref "TP2") (pin "P$1") (pinfunction "P$1_P$1") (pintype "bidirectional"))
    )
    (net (code "61") (name "Net-(MS1-GPIO13-Pad25')") (class "Default")
      (node (ref "MS1") (pin "25") (pinfunction "GPIO13_25") (pintype "bidirectional"))
      (node (ref "MS1") (pin "25'") (pinfunction "GPIO13_25'") (pintype "bidirectional"))
      (node (ref "TP3") (pin "P$1") (pinfunction "P$1_P$1") (pintype "bidirectional"))
    )
    (net (code "62") (name "VBAT") (class "Default")
      (node (ref "BAT") (pin "P$1") (pinfunction "P$1_P$1") (pintype "bidirectional"))
      (node (ref "MS1") (pin "28") (pinfunction "VBAT_28") (pintype "power_in"))
      (node (ref "MS1") (pin "28'") (pinfunction "VBAT_28'") (pintype "power_in"))
    )
    (net (code "63") (name "VBUS") (class "Default")
      (node (ref "MS1") (pin "26") (pinfunction "USB_26") (pintype "power_in"))
      (node (ref "MS1") (pin "26'") (pinfunction "USB_26'") (pintype "power_in"))
      (node (ref "USB") (pin "P$1") (pinfunction "P$1_P$1") (pintype "bidirectional"))
    )
    (net (code "64") (name "unconnected-(I2CB-MT-PadNC1)") (class "Default")
      (node (ref "I2C") (pin "NC1") (pinfunction "MT_NC1") (pintype "bidirectional"))
    )
    (net (code "65") (name "unconnected-(I2CC-MT-PadNC2)") (class "Default")
      (node (ref "I2C") (pin "NC2") (pinfunction "MT_NC2") (pintype "bidirectional"))
    )
    (net (code "66") (name "unconnected-(IC2-NC-Pad3)") (class "Default")
      (node (ref "IC2") (pin "3") (pinfunction "NC_3") (pintype "no_connect"))
    )
    (net (code "67") (name "unconnected-(MICROSD-CARD_DETECT-PadCD1)") (class "Default")
      (node (ref "MICROSD") (pin "CD1") (pinfunction "CARD_DETECT_CD1") (pintype "passive"))
    )
    (net (code "68") (name "unconnected-(MICROSD-DAT1-Pad8)") (class "Default")
      (node (ref "MICROSD") (pin "8") (pinfunction "DAT1_8") (pintype "bidirectional"))
    )
    (net (code "69") (name "unconnected-(MICROSD-DAT2-Pad1)") (class "Default")
      (node (ref "MICROSD") (pin "1") (pinfunction "DAT2_1") (pintype "bidirectional"))
    )
    (net (code "70") (name "unconnected-(SW1-O-PadP$1)") (class "Default")
      (node (ref "SW1") (pin "P$1") (pinfunction "O_P$1") (pintype "passive"))
    )
    (net (code "71") (name "unconnected-(U$2-HLT_CTL-Pad1)") (class "Default")
      (node (ref "U$2") (pin "1") (pinfunction "HLT_CTL_1") (pintype "bidirectional"))
    )
  )
)
